# Accessory_Breakout_X1.net
KiCad netlist of a schematic drawn in Altium Designer
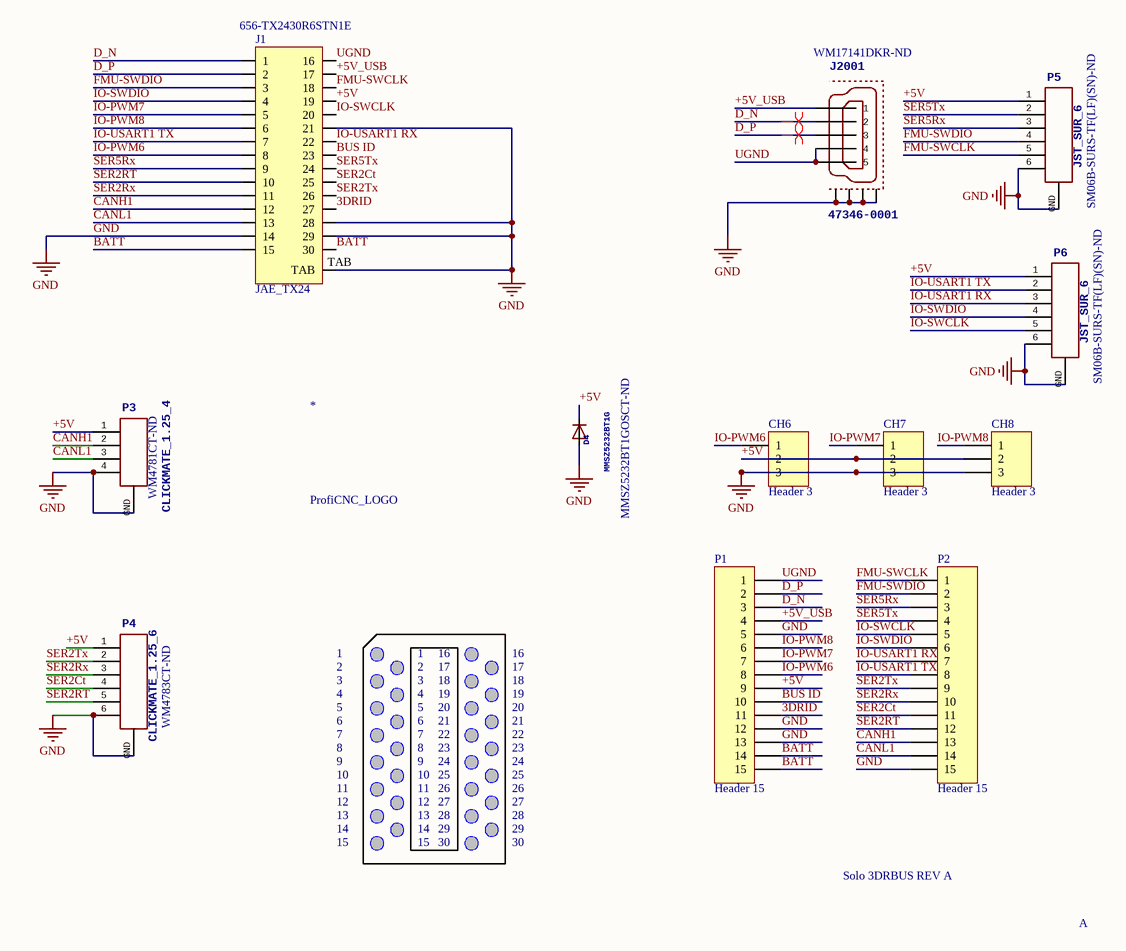
[diagram p0: Accessory_Breakout_X1.SchDoc]

(export (version "E")
  (design (tool "Eeschema 10.0.6"))
  (components
    (comp (ref "*")
      (value "ProfiCNC_LOGO")
      (footprint "ProfiCNC_medium")
      (libsource (lib "ProfiCNC") (part "ProfiCNC_LOGO"))
    )
    (comp (ref "CH6")
      (value "Header 3")
      (footprint "HDR1X3")
      (description "Header, 3-Pin")
      (fields (field (name "PUBLISHER") "Altium Limited"))
      (libsource (lib "Miscellaneous Connectors") (part "Header 3"))
    )
    (comp (ref "CH7")
      (value "Header 3")
      (footprint "HDR1X3")
      (description "Header, 3-Pin")
      (fields (field (name "PUBLISHER") "Altium Limited"))
      (libsource (lib "Miscellaneous Connectors") (part "Header 3"))
    )
    (comp (ref "CH8")
      (value "Header 3")
      (footprint "HDR1X3")
      (description "Header, 3-Pin")
      (fields (field (name "PUBLISHER") "Altium Limited"))
      (libsource (lib "Miscellaneous Connectors") (part "Header 3"))
    )
    (comp (ref "D4")
      (value "MMSZ5232BT1G")
      (footprint "SOD-123")
      (description "DIODE ZENER 5.6V 500MW SOD123")
      (fields
        (field (name "SUPPLIER PART NUMBER 1") "MMSZ5232BT1GOSCT-ND")
        (field (name "3DR_PARTNO") "ECM0536")
      )
      (libsource (lib "adafruit") (part "DIODESOD-123"))
    )
    (comp (ref "J1")
      (value "JAE_TX24")
      (footprint "JAE TX24")
      (fields (field (name "SUPPLIER PART NUMBER 1") "656-TX2430R6STN1E"))
      (libsource (lib "3DR") (part "JAE_TX24"))
    )
    (comp (ref "J2001")
      (value "47346-0001")
      (footprint "MOLEX-47346-0001")
      (description "MICRO USB B, BOTTOM MOUNT")
      (fields
        (field (name "SUPPLIER PART NUMBER 1") "WM17141DKR-ND")
        (field (name "3DR_PARTNO") "ECM0486")
        (field (name "PARTNO") "0473460001")
      )
      (libsource (lib "pixhawk2") (part "MOLEX-47346-0001"))
    )
    (comp (ref "P1")
      (value "Header 15")
      (footprint "HDR1X15")
      (description "Header, 15-Pin")
      (fields (field (name "PUBLISHER") "Altium Limited"))
      (libsource (lib "Miscellaneous Connectors") (part "Header 15"))
    )
    (comp (ref "P2")
      (value "Header 15")
      (footprint "HDR1X15")
      (description "Header, 15-Pin")
      (fields (field (name "PUBLISHER") "Altium Limited"))
      (libsource (lib "") (part "Header 15_1"))
    )
    (comp (ref "P3")
      (value "CLICKMATE_1.25_4")
      (footprint "CLICKMATE_V4")
      (description "Connector, Rcpt, 4Pos, 1.25MM, W/B, VERT, SMD, Tin")
      (fields (field (name "SUPPLIER PART NUMBER 1") "WM4781CT-ND") (field (name "3DR_PARTNO") "PRT0441"))
      (libsource (lib "PCA_0005_FULL_CB_REV_A") (part "CLICKMATE_1.25_4"))
    )
    (comp (ref "P4")
      (value "CLICKMATE_1.25_6")
      (footprint "CLICKMATE_V6")
      (description "Connector, Rcpt, 6Pos, 1.25MM, W/B, VERT, SMD, Tin")
      (fields (field (name "SUPPLIER PART NUMBER 1") "WM4783CT-ND") (field (name "3DR_PARTNO") "PRT0439"))
      (libsource (lib "PCA_0005_FULL_CB_REV_A") (part "CLICKMATE_1.25_6"))
    )
    (comp (ref "P5")
      (value "JST_SUR_6")
      (footprint "JST_SUR_H6")
      (description "Connector, Header, 6Pos, .8mm IDC, R/A, SMD, Tin")
      (fields
        (field (name "SUPPLIER PART NUMBER 1") "SM06B-SURS-TF(LF)(SN)-ND")
        (field (name "3DR_PARTNO") "PRT0442")
      )
      (libsource (lib "PCA_0005_FULL_CB_REV_A") (part "JST_SUR_6"))
    )
    (comp (ref "P6")
      (value "JST_SUR_6")
      (footprint "JST_SUR_H6")
      (description "Connector, Header, 6Pos, .8mm IDC, R/A, SMD, Tin")
      (fields
        (field (name "SUPPLIER PART NUMBER 1") "SM06B-SURS-TF(LF)(SN)-ND")
        (field (name "3DR_PARTNO") "PRT0442")
      )
      (libsource (lib "PCA_0005_FULL_CB_REV_A") (part "JST_SUR_6"))
    )
  )
  (nets
    (net (code "1") (name "/+5V") (class "Default")
      (node (ref "CH6") (pin "2") (pinfunction "2_2") (pintype "passive"))
      (node (ref "CH7") (pin "2") (pinfunction "2_2") (pintype "passive"))
      (node (ref "CH8") (pin "2") (pinfunction "2_2") (pintype "passive"))
      (node (ref "D4") (pin "C") (pinfunction "C_C") (pintype "passive"))
      (node (ref "J1") (pin "19") (pinfunction "19_19") (pintype "passive"))
      (node (ref "P1") (pin "9") (pinfunction "9_9") (pintype "passive"))
      (node (ref "P3") (pin "1") (pinfunction "1_1") (pintype "passive"))
      (node (ref "P4") (pin "1") (pinfunction "1_1") (pintype "passive"))
      (node (ref "P5") (pin "1") (pinfunction "1_1") (pintype "passive"))
      (node (ref "P6") (pin "1") (pinfunction "1_1") (pintype "passive"))
    )
    (net (code "2") (name "/+5V_USB") (class "Default")
      (node (ref "J1") (pin "17") (pinfunction "17_17") (pintype "passive"))
      (node (ref "J2001") (pin "VBUS") (pinfunction "1_VBUS") (pintype "open_emitter"))
      (node (ref "P1") (pin "4") (pinfunction "4_4") (pintype "passive"))
    )
    (net (code "3") (name "/3DRID") (class "Default")
      (node (ref "J1") (pin "27") (pinfunction "27_27") (pintype "passive"))
      (node (ref "P1") (pin "11") (pinfunction "11_11") (pintype "passive"))
    )
    (net (code "4") (name "/BATT") (class "Default")
      (node (ref "J1") (pin "15") (pinfunction "15_15") (pintype "passive"))
      (node (ref "J1") (pin "30") (pinfunction "30_30") (pintype "passive"))
      (node (ref "P1") (pin "14") (pinfunction "14_14") (pintype "passive"))
      (node (ref "P1") (pin "15") (pinfunction "15_15") (pintype "passive"))
    )
    (net (code "5") (name "/BUS ID") (class "Default")
      (node (ref "J1") (pin "23") (pinfunction "23_23") (pintype "passive"))
      (node (ref "P1") (pin "10") (pinfunction "10_10") (pintype "passive"))
    )
    (net (code "6") (name "/CANH1") (class "Default")
      (node (ref "J1") (pin "12") (pinfunction "12_12") (pintype "passive"))
      (node (ref "P2") (pin "13") (pinfunction "13_13") (pintype "passive"))
      (node (ref "P3") (pin "2") (pinfunction "2_2") (pintype "passive"))
    )
    (net (code "7") (name "/CANL1") (class "Default")
      (node (ref "J1") (pin "13") (pinfunction "13_13") (pintype "passive"))
      (node (ref "P2") (pin "14") (pinfunction "14_14") (pintype "passive"))
      (node (ref "P3") (pin "3") (pinfunction "3_3") (pintype "passive"))
    )
    (net (code "8") (name "/D_N") (class "Default")
      (node (ref "J1") (pin "1") (pinfunction "1_1") (pintype "passive"))
      (node (ref "J2001") (pin "D-") (pinfunction "2_D-") (pintype "passive"))
      (node (ref "P1") (pin "3") (pinfunction "3_3") (pintype "passive"))
    )
    (net (code "9") (name "/D_P") (class "Default")
      (node (ref "J1") (pin "2") (pinfunction "2_2") (pintype "passive"))
      (node (ref "J2001") (pin "D+") (pinfunction "3_D+") (pintype "passive"))
      (node (ref "P1") (pin "2") (pinfunction "2_2") (pintype "passive"))
    )
    (net (code "10") (name "/FMU-SWCLK") (class "Default")
      (node (ref "J1") (pin "18") (pinfunction "18_18") (pintype "passive"))
      (node (ref "P2") (pin "1") (pinfunction "1_1") (pintype "passive"))
      (node (ref "P5") (pin "5") (pinfunction "5_5") (pintype "passive"))
    )
    (net (code "11") (name "/FMU-SWDIO") (class "Default")
      (node (ref "J1") (pin "3") (pinfunction "3_3") (pintype "passive"))
      (node (ref "P2") (pin "2") (pinfunction "2_2") (pintype "passive"))
      (node (ref "P5") (pin "4") (pinfunction "4_4") (pintype "passive"))
    )
    (net (code "12") (name "/IO-PWM6") (class "Default")
      (node (ref "CH6") (pin "1") (pinfunction "1_1") (pintype "passive"))
      (node (ref "J1") (pin "8") (pinfunction "8_8") (pintype "passive"))
      (node (ref "P1") (pin "8") (pinfunction "8_8") (pintype "passive"))
    )
    (net (code "13") (name "/IO-PWM7") (class "Default")
      (node (ref "CH7") (pin "1") (pinfunction "1_1") (pintype "passive"))
      (node (ref "J1") (pin "5") (pinfunction "5_5") (pintype "passive"))
      (node (ref "P1") (pin "7") (pinfunction "7_7") (pintype "passive"))
    )
    (net (code "14") (name "/IO-PWM8") (class "Default")
      (node (ref "CH8") (pin "1") (pinfunction "1_1") (pintype "passive"))
      (node (ref "J1") (pin "6") (pinfunction "6_6") (pintype "passive"))
      (node (ref "P1") (pin "6") (pinfunction "6_6") (pintype "passive"))
    )
    (net (code "15") (name "/IO-SWCLK") (class "Default")
      (node (ref "J1") (pin "20") (pinfunction "20_20") (pintype "passive"))
      (node (ref "P2") (pin "5") (pinfunction "5_5") (pintype "passive"))
      (node (ref "P6") (pin "5") (pinfunction "5_5") (pintype "passive"))
    )
    (net (code "16") (name "/IO-SWDIO") (class "Default")
      (node (ref "J1") (pin "4") (pinfunction "4_4") (pintype "passive"))
      (node (ref "P2") (pin "6") (pinfunction "6_6") (pintype "passive"))
      (node (ref "P6") (pin "4") (pinfunction "4_4") (pintype "passive"))
    )
    (net (code "17") (name "/IO-USART1 RX") (class "Default")
      (node (ref "J1") (pin "22") (pinfunction "22_22") (pintype "passive"))
      (node (ref "P2") (pin "7") (pinfunction "7_7") (pintype "passive"))
      (node (ref "P6") (pin "3") (pinfunction "3_3") (pintype "passive"))
    )
    (net (code "18") (name "/IO-USART1 TX") (class "Default")
      (node (ref "J1") (pin "7") (pinfunction "7_7") (pintype "passive"))
      (node (ref "P2") (pin "8") (pinfunction "8_8") (pintype "passive"))
      (node (ref "P6") (pin "2") (pinfunction "2_2") (pintype "passive"))
    )
    (net (code "19") (name "/SER2Ct") (class "Default")
      (node (ref "J1") (pin "25") (pinfunction "25_25") (pintype "passive"))
      (node (ref "P2") (pin "11") (pinfunction "11_11") (pintype "passive"))
      (node (ref "P4") (pin "4") (pinfunction "4_4") (pintype "passive"))
    )
    (net (code "20") (name "/SER2RT") (class "Default")
      (node (ref "J1") (pin "10") (pinfunction "10_10") (pintype "passive"))
      (node (ref "P2") (pin "12") (pinfunction "12_12") (pintype "passive"))
      (node (ref "P4") (pin "5") (pinfunction "5_5") (pintype "passive"))
    )
    (net (code "21") (name "/SER2Rx") (class "Default")
      (node (ref "J1") (pin "11") (pinfunction "11_11") (pintype "passive"))
      (node (ref "P2") (pin "10") (pinfunction "10_10") (pintype "passive"))
      (node (ref "P4") (pin "3") (pinfunction "3_3") (pintype "passive"))
    )
    (net (code "22") (name "/SER2Tx") (class "Default")
      (node (ref "J1") (pin "26") (pinfunction "26_26") (pintype "passive"))
      (node (ref "P2") (pin "9") (pinfunction "9_9") (pintype "passive"))
      (node (ref "P4") (pin "2") (pinfunction "2_2") (pintype "passive"))
    )
    (net (code "23") (name "/SER5Rx") (class "Default")
      (node (ref "J1") (pin "9") (pinfunction "9_9") (pintype "passive"))
      (node (ref "P2") (pin "3") (pinfunction "3_3") (pintype "passive"))
      (node (ref "P5") (pin "3") (pinfunction "3_3") (pintype "passive"))
    )
    (net (code "24") (name "/SER5Tx") (class "Default")
      (node (ref "J1") (pin "24") (pinfunction "24_24") (pintype "passive"))
      (node (ref "P2") (pin "4") (pinfunction "4_4") (pintype "passive"))
      (node (ref "P5") (pin "2") (pinfunction "2_2") (pintype "passive"))
    )
    (net (code "25") (name "/UGND") (class "Default")
      (node (ref "J1") (pin "16") (pinfunction "16_16") (pintype "passive"))
      (node (ref "J2001") (pin "GND") (pinfunction "5_GND") (pintype "open_emitter"))
      (node (ref "J2001") (pin "ID") (pinfunction "4_ID") (pintype "passive"))
      (node (ref "P1") (pin "1") (pinfunction "1_1") (pintype "passive"))
    )
    (net (code "26") (name "GND") (class "Default")
      (node (ref "CH6") (pin "3") (pinfunction "3_3") (pintype "passive"))
      (node (ref "CH7") (pin "3") (pinfunction "3_3") (pintype "passive"))
      (node (ref "CH8") (pin "3") (pinfunction "3_3") (pintype "passive"))
      (node (ref "D4") (pin "A") (pinfunction "A_A") (pintype "passive"))
      (node (ref "J1") (pin "14") (pinfunction "14_14") (pintype "passive"))
      (node (ref "J1") (pin "21") (pinfunction "21_21") (pintype "passive"))
      (node (ref "J1") (pin "28") (pinfunction "28_28") (pintype "passive"))
      (node (ref "J1") (pin "29") (pinfunction "29_29") (pintype "passive"))
      (node (ref "J1") (pin "TAB") (pinfunction "TAB_TAB") (pintype "passive"))
      (node (ref "J2001") (pin "GND1") (pinfunction "GND1_GND1") (pintype "passive"))
      (node (ref "J2001") (pin "GND2") (pinfunction "GND2_GND2") (pintype "passive"))
      (node (ref "J2001") (pin "GND3") (pinfunction "GND3_GND3") (pintype "passive"))
      (node (ref "J2001") (pin "GND4") (pinfunction "GND4_GND4") (pintype "passive"))
      (node (ref "P1") (pin "12") (pinfunction "12_12") (pintype "passive"))
      (node (ref "P1") (pin "13") (pinfunction "13_13") (pintype "passive"))
      (node (ref "P1") (pin "5") (pinfunction "5_5") (pintype "passive"))
      (node (ref "P2") (pin "15") (pinfunction "15_15") (pintype "passive"))
      (node (ref "P3") (pin "4") (pinfunction "4_4") (pintype "passive"))
      (node (ref "P3") (pin "GND") (pinfunction "GND_GND") (pintype "passive"))
      (node (ref "P4") (pin "6") (pinfunction "6_6") (pintype "passive"))
      (node (ref "P4") (pin "GND") (pinfunction "GND_GND") (pintype "passive"))
      (node (ref "P5") (pin "6") (pinfunction "6_6") (pintype "passive"))
      (node (ref "P5") (pin "GND") (pinfunction "GND_GND") (pintype "passive"))
      (node (ref "P6") (pin "6") (pinfunction "6_6") (pintype "passive"))
      (node (ref "P6") (pin "GND") (pinfunction "GND_GND") (pintype "passive"))
    )
  )
)
